# PI.net
KiCad netlist of a schematic drawn in Altium Designer
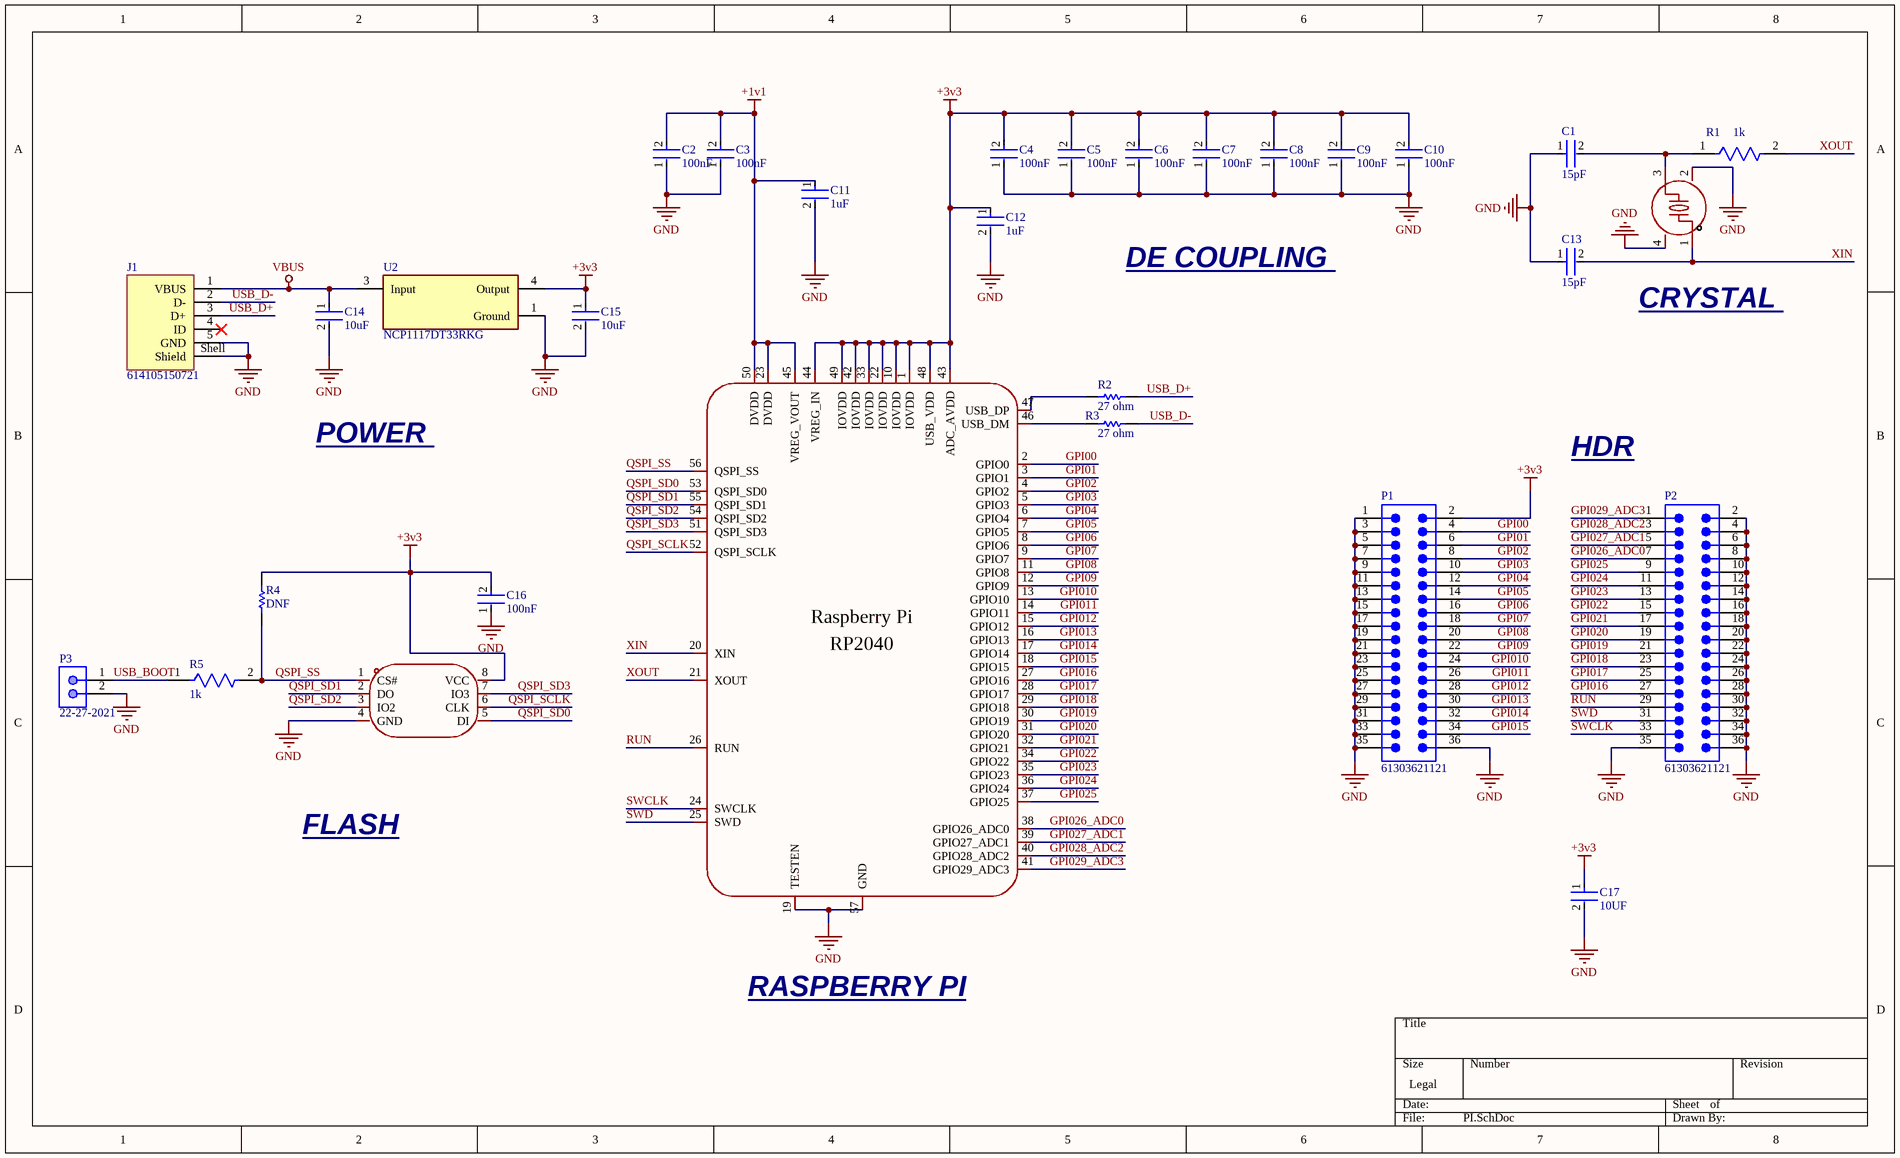
[diagram p0: PI.SchDoc]

(export (version "E")
  (design (tool "Eeschema 10.0.6"))
  (components
    (comp (ref "C1")
      (value "15pF")
      (footprint "FP-C0402-BB-MFG")
      (description "CAP CER 15PF 16V 5% NP0 0402")
      (fields (field (name "MANUFACTURER") "Kemet") (field (name "TOLERANCE") "0.05"))
      (libsource (lib "Altium Content Vault") (part "b4654b650e69147ec39a6b967a45e02"))
    )
    (comp (ref "C2")
      (value "100nF")
      (footprint "FP-GRM15-MFG")
      (description "CAP CER 0.1UF 16V X7R 0402")
      (fields (field (name "MANUFACTURER PART NUMBER") "GRM155R71C104KA88D") (field (name "TOLERANCE") "10%"))
      (libsource (lib "Altium Content Vault") (part "236180d848d6139a670b325ea6854c9"))
    )
    (comp (ref "C3")
      (value "100nF")
      (footprint "FP-GRM15-MFG")
      (description "CAP CER 0.1UF 16V X7R 0402")
      (fields (field (name "MANUFACTURER PART NUMBER") "GRM155R71C104KA88D") (field (name "TOLERANCE") "10%"))
      (libsource (lib "Altium Content Vault") (part "236180d848d6139a670b325ea6854c9"))
    )
    (comp (ref "C4")
      (value "100nF")
      (footprint "FP-GRM15-MFG")
      (description "CAP CER 0.1UF 16V X7R 0402")
      (fields (field (name "MANUFACTURER PART NUMBER") "GRM155R71C104KA88D") (field (name "TOLERANCE") "10%"))
      (libsource (lib "Altium Content Vault") (part "236180d848d6139a670b325ea6854c9"))
    )
    (comp (ref "C5")
      (value "100nF")
      (footprint "FP-GRM15-MFG")
      (description "CAP CER 0.1UF 16V X7R 0402")
      (fields (field (name "MANUFACTURER PART NUMBER") "GRM155R71C104KA88D") (field (name "TOLERANCE") "10%"))
      (libsource (lib "Altium Content Vault") (part "236180d848d6139a670b325ea6854c9"))
    )
    (comp (ref "C6")
      (value "100nF")
      (footprint "FP-GRM15-MFG")
      (description "CAP CER 0.1UF 16V X7R 0402")
      (fields (field (name "MANUFACTURER PART NUMBER") "GRM155R71C104KA88D") (field (name "TOLERANCE") "10%"))
      (libsource (lib "Altium Content Vault") (part "236180d848d6139a670b325ea6854c9"))
    )
    (comp (ref "C7")
      (value "100nF")
      (footprint "FP-GRM15-MFG")
      (description "CAP CER 0.1UF 16V X7R 0402")
      (fields (field (name "MANUFACTURER PART NUMBER") "GRM155R71C104KA88D") (field (name "TOLERANCE") "10%"))
      (libsource (lib "Altium Content Vault") (part "236180d848d6139a670b325ea6854c9"))
    )
    (comp (ref "C8")
      (value "100nF")
      (footprint "FP-GRM15-MFG")
      (description "CAP CER 0.1UF 16V X7R 0402")
      (fields (field (name "MANUFACTURER PART NUMBER") "GRM155R71C104KA88D") (field (name "TOLERANCE") "10%"))
      (libsource (lib "Altium Content Vault") (part "236180d848d6139a670b325ea6854c9"))
    )
    (comp (ref "C9")
      (value "100nF")
      (footprint "FP-GRM15-MFG")
      (description "CAP CER 0.1UF 16V X7R 0402")
      (fields (field (name "MANUFACTURER PART NUMBER") "GRM155R71C104KA88D") (field (name "TOLERANCE") "10%"))
      (libsource (lib "Altium Content Vault") (part "236180d848d6139a670b325ea6854c9"))
    )
    (comp (ref "C10")
      (value "100nF")
      (footprint "FP-GRM15-MFG")
      (description "CAP CER 0.1UF 16V X7R 0402")
      (fields (field (name "MANUFACTURER PART NUMBER") "GRM155R71C104KA88D") (field (name "TOLERANCE") "10%"))
      (libsource (lib "Altium Content Vault") (part "236180d848d6139a670b325ea6854c9"))
    )
    (comp (ref "C11")
      (value "1uF")
      (footprint "FP-C0805C105Z4VACTU-MFG")
      (description "CAP CER 1UF 16V Y5V 0805")
      (fields (field (name "VOLTAGE") "16V") (field (name "TOLERANCE") "80%"))
      (libsource (lib "Altium Content Vault") (part "02cd4be3c70576c341d710602a673aa"))
    )
    (comp (ref "C12")
      (value "1uF")
      (footprint "FP-C0805C105Z4VACTU-MFG")
      (description "CAP CER 1UF 16V Y5V 0805")
      (fields (field (name "VOLTAGE") "16V") (field (name "TOLERANCE") "80%"))
      (libsource (lib "Altium Content Vault") (part "02cd4be3c70576c341d710602a673aa"))
    )
    (comp (ref "C13")
      (value "15pF")
      (footprint "FP-C0402-BB-MFG")
      (description "CAP CER 15PF 16V 5% NP0 0402")
      (fields (field (name "MANUFACTURER") "Kemet") (field (name "TOLERANCE") "0.05"))
      (libsource (lib "Altium Content Vault") (part "b4654b650e69147ec39a6b967a45e02"))
    )
    (comp (ref "C14")
      (value "10uF")
      (footprint "FP-1206-L_3_2_0_2-W_1_6_0-IPC_C")
      (description "General Purpose Ceramic Capacitor, 1206, 10uF, 10%, X7R, 15%, 16V")
      (fields (field (name "VOLTAGE") "16V") (field (name "TOLERANCE") "10%"))
      (libsource (lib "Altium Content Vault") (part "b4654b650e69147ec39a6b967a45e02"))
    )
    (comp (ref "C15")
      (value "10uF")
      (footprint "FP-1206-L_3_2_0_2-W_1_6_0-IPC_C")
      (description "General Purpose Ceramic Capacitor, 1206, 10uF, 10%, X7R, 15%, 16V")
      (fields (field (name "VOLTAGE") "16V") (field (name "TOLERANCE") "10%"))
      (libsource (lib "Altium Content Vault") (part "b4654b650e69147ec39a6b967a45e02"))
    )
    (comp (ref "C16")
      (value "100nF")
      (footprint "FP-GRM15-MFG")
      (description "CAP CER 0.1UF 16V X7R 0402")
      (fields (field (name "MANUFACTURER PART NUMBER") "GRM155R71C104KA88D") (field (name "TOLERANCE") "10%"))
      (libsource (lib "Altium Content Vault") (part "236180d848d6139a670b325ea6854c9"))
    )
    (comp (ref "C17")
      (value "10UF")
      (footprint "FP-0603-L_1_6_0_2-W_0_8_0-MFG")
      (description "Multilayer Ceramic Capacitor 10uF 16V X5R 20% SMD 0603 T/R")
      (fields (field (name "TOLERANCE") "20%"))
      (libsource (lib "Altium Content Vault") (part "b4654b650e69147ec39a6b967a45e02"))
    )
    (comp (ref "J1")
      (value "614105150721")
      (footprint "614105150721")
      (libsource (lib "Altium Content Vault") (part "Micro USB 2.0_Type B_Receptacle_1 Port"))
    )
    (comp (ref "P1")
      (value "61303621121")
      (footprint "61303621121")
      (libsource (lib "Altium Content Vault") (part "Header_Male_2R_36P"))
    )
    (comp (ref "P2")
      (value "61303621121")
      (footprint "61303621121")
      (libsource (lib "Altium Content Vault") (part "Header_Male_2R_36P"))
    )
    (comp (ref "P3")
      (value "22-27-2021")
      (footprint "MOLX-22-27-2021_V")
      (fields (field (name "MANUFACTURER") "Molex") (field (name "PARTNUMBER") "0022272021"))
      (libsource (lib "Altium Content Vault") (part "CN-1P-M-R2"))
    )
    (comp (ref "R1")
      (value "1k")
      (footprint "FP-AC0603-IPC_B")
      (description "RES 1kΩ 1.00% 0.1W 0603")
      (fields (field (name "TOLERANCE") "1%"))
      (libsource (lib "Altium Content Vault") (part "1029c3af85768c4190bb7ad29bc67b5"))
    )
    (comp (ref "R2")
      (value "27 ohm")
      (footprint "RESC1005X40X25LL05T10")
      (fields (field (name "PART NUMBER") "RC0402FR-0727RL") (field (name "MANUFACTURER") "Yageo / Phycomp"))
      (libsource (lib "Altium Content Vault") (part "RES"))
    )
    (comp (ref "R3")
      (value "27 ohm")
      (footprint "RESC1005X40X25LL05T10")
      (fields (field (name "PART NUMBER") "RC0402FR-0727RL") (field (name "MANUFACTURER") "Yageo / Phycomp"))
      (libsource (lib "Altium Content Vault") (part "RES"))
    )
    (comp (ref "R4")
      (value "DNF")
      (footprint "RESC2013X50X30LL20T20")
      (fields (field (name "MANUFACTURER") "Vishay Dale") (field (name "PART NUMBER") "CRCW08050000Z0EA"))
      (libsource (lib "Altium Content Vault") (part "RES"))
    )
    (comp (ref "R5")
      (value "1k")
      (footprint "FP-AC0603-IPC_B")
      (description "RES 1kΩ 1.00% 0.1W 0603")
      (fields (field (name "TOLERANCE") "1%"))
      (libsource (lib "Altium Content Vault") (part "1029c3af85768c4190bb7ad29bc67b5"))
    )
    (comp (ref "U1")
      (value "ABM8-272-T3")
      (footprint "CRYSTAL-SMD_4P-L3.2-W2.5-BL")
      (fields (field (name "MANUFACTURER") "ABRACON"))
      (libsource (lib "RP") (part "ABM8-272-T3_C20625731"))
    )
    (comp (ref "U2")
      (value "NCP1117DT33RKG")
      (footprint "FP-369C-MFG")
      (description "IC REG LINEAR 3.3V 1A DPAK-3")
      (libsource (lib "Altium Content Vault") (part "42bbf5c8e4ae9854764b07c869d8ce2"))
    )
    (comp (ref "U3")
      (value "RP2040")
      (footprint "LQFN-56_L7.0-W7.0-P0.4-EP")
      (fields (field (name "MANUFACTURER") "Raspberry Pi(树莓派)"))
      (libsource (lib "RP") (part "RP2040_C2040"))
    )
    (comp (ref "U4")
      (value "W25Q128JVSIQ")
      (footprint "SOIC-8_L5.3-W5.3-P1.27-LS8.0-BL")
      (fields (field (name "MANUFACTURER") "WINBOND(华邦)"))
      (libsource (lib "RP") (part "W25Q128JVSIQ"))
    )
  )
  (nets
    (net (code "1") (name "+1v1") (class "Default")
      (node (ref "C11") (pin "1") (pinfunction "1_1") (pintype "passive"))
      (node (ref "C2") (pin "2") (pinfunction "2_2") (pintype "passive"))
      (node (ref "C3") (pin "2") (pinfunction "2_2") (pintype "passive"))
      (node (ref "U3") (pin "23") (pinfunction "DVDD_23") (pintype "passive"))
      (node (ref "U3") (pin "45") (pinfunction "VREG_VOUT_45") (pintype "passive"))
      (node (ref "U3") (pin "50") (pinfunction "DVDD_50") (pintype "passive"))
    )
    (net (code "2") (name "+3v3") (class "Default")
      (node (ref "C10") (pin "2") (pinfunction "2_2") (pintype "passive"))
      (node (ref "C12") (pin "1") (pinfunction "1_1") (pintype "passive"))
      (node (ref "C15") (pin "1") (pinfunction "1_1") (pintype "passive"))
      (node (ref "C16") (pin "2") (pinfunction "2_2") (pintype "passive"))
      (node (ref "C17") (pin "1") (pinfunction "1_1") (pintype "passive"))
      (node (ref "C4") (pin "2") (pinfunction "2_2") (pintype "passive"))
      (node (ref "C5") (pin "2") (pinfunction "2_2") (pintype "passive"))
      (node (ref "C6") (pin "2") (pinfunction "2_2") (pintype "passive"))
      (node (ref "C7") (pin "2") (pinfunction "2_2") (pintype "passive"))
      (node (ref "C8") (pin "2") (pinfunction "2_2") (pintype "passive"))
      (node (ref "C9") (pin "2") (pinfunction "2_2") (pintype "passive"))
      (node (ref "P1") (pin "2") (pinfunction "2_2") (pintype "passive"))
      (node (ref "R4") (pin "2") (pinfunction "2_2") (pintype "passive"))
      (node (ref "U2") (pin "4") (pinfunction "Output_4") (pintype "power_in"))
      (node (ref "U3") (pin "1") (pinfunction "IOVDD_1") (pintype "passive"))
      (node (ref "U3") (pin "10") (pinfunction "IOVDD_10") (pintype "passive"))
      (node (ref "U3") (pin "22") (pinfunction "IOVDD_22") (pintype "passive"))
      (node (ref "U3") (pin "33") (pinfunction "IOVDD_33") (pintype "passive"))
      (node (ref "U3") (pin "42") (pinfunction "IOVDD_42") (pintype "passive"))
      (node (ref "U3") (pin "43") (pinfunction "ADC_AVDD_43") (pintype "passive"))
      (node (ref "U3") (pin "44") (pinfunction "VREG_IN_44") (pintype "passive"))
      (node (ref "U3") (pin "48") (pinfunction "USB_VDD_48") (pintype "passive"))
      (node (ref "U3") (pin "49") (pinfunction "IOVDD_49") (pintype "passive"))
      (node (ref "U4") (pin "8") (pinfunction "VCC_8") (pintype "passive"))
    )
    (net (code "3") (name "/GPI00") (class "Default")
      (node (ref "P1") (pin "4") (pinfunction "4_4") (pintype "passive"))
      (node (ref "U3") (pin "2") (pinfunction "GPIO0_2") (pintype "passive"))
    )
    (net (code "4") (name "/GPI01") (class "Default")
      (node (ref "P1") (pin "6") (pinfunction "6_6") (pintype "passive"))
      (node (ref "U3") (pin "3") (pinfunction "GPIO1_3") (pintype "passive"))
    )
    (net (code "5") (name "/GPI02") (class "Default")
      (node (ref "P1") (pin "8") (pinfunction "8_8") (pintype "passive"))
      (node (ref "U3") (pin "4") (pinfunction "GPIO2_4") (pintype "passive"))
    )
    (net (code "6") (name "/GPI03") (class "Default")
      (node (ref "P1") (pin "10") (pinfunction "10_10") (pintype "passive"))
      (node (ref "U3") (pin "5") (pinfunction "GPIO3_5") (pintype "passive"))
    )
    (net (code "7") (name "/GPI04") (class "Default")
      (node (ref "P1") (pin "12") (pinfunction "12_12") (pintype "passive"))
      (node (ref "U3") (pin "6") (pinfunction "GPIO4_6") (pintype "passive"))
    )
    (net (code "8") (name "/GPI05") (class "Default")
      (node (ref "P1") (pin "14") (pinfunction "14_14") (pintype "passive"))
      (node (ref "U3") (pin "7") (pinfunction "GPIO5_7") (pintype "passive"))
    )
    (net (code "9") (name "/GPI06") (class "Default")
      (node (ref "P1") (pin "16") (pinfunction "16_16") (pintype "passive"))
      (node (ref "U3") (pin "8") (pinfunction "GPIO6_8") (pintype "passive"))
    )
    (net (code "10") (name "/GPI07") (class "Default")
      (node (ref "P1") (pin "18") (pinfunction "18_18") (pintype "passive"))
      (node (ref "U3") (pin "9") (pinfunction "GPIO7_9") (pintype "passive"))
    )
    (net (code "11") (name "/GPI08") (class "Default")
      (node (ref "P1") (pin "20") (pinfunction "20_20") (pintype "passive"))
      (node (ref "U3") (pin "11") (pinfunction "GPIO8_11") (pintype "passive"))
    )
    (net (code "12") (name "/GPI09") (class "Default")
      (node (ref "P1") (pin "22") (pinfunction "22_22") (pintype "passive"))
      (node (ref "U3") (pin "12") (pinfunction "GPIO9_12") (pintype "passive"))
    )
    (net (code "13") (name "/GPI010") (class "Default")
      (node (ref "P1") (pin "24") (pinfunction "24_24") (pintype "passive"))
      (node (ref "U3") (pin "13") (pinfunction "GPIO10_13") (pintype "passive"))
    )
    (net (code "14") (name "/GPI011") (class "Default")
      (node (ref "P1") (pin "26") (pinfunction "26_26") (pintype "passive"))
      (node (ref "U3") (pin "14") (pinfunction "GPIO11_14") (pintype "passive"))
    )
    (net (code "15") (name "/GPI012") (class "Default")
      (node (ref "P1") (pin "28") (pinfunction "28_28") (pintype "passive"))
      (node (ref "U3") (pin "15") (pinfunction "GPIO12_15") (pintype "passive"))
    )
    (net (code "16") (name "/GPI013") (class "Default")
      (node (ref "P1") (pin "30") (pinfunction "30_30") (pintype "passive"))
      (node (ref "U3") (pin "16") (pinfunction "GPIO13_16") (pintype "passive"))
    )
    (net (code "17") (name "/GPI014") (class "Default")
      (node (ref "P1") (pin "32") (pinfunction "32_32") (pintype "passive"))
      (node (ref "U3") (pin "17") (pinfunction "GPIO14_17") (pintype "passive"))
    )
    (net (code "18") (name "/GPI015") (class "Default")
      (node (ref "P1") (pin "34") (pinfunction "34_34") (pintype "passive"))
      (node (ref "U3") (pin "18") (pinfunction "GPIO15_18") (pintype "passive"))
    )
    (net (code "19") (name "/GPI016") (class "Default")
      (node (ref "P2") (pin "27") (pinfunction "27_27") (pintype "passive"))
      (node (ref "U3") (pin "27") (pinfunction "GPIO16_27") (pintype "passive"))
    )
    (net (code "20") (name "/GPI017") (class "Default")
      (node (ref "P2") (pin "25") (pinfunction "25_25") (pintype "passive"))
      (node (ref "U3") (pin "28") (pinfunction "GPIO17_28") (pintype "passive"))
    )
    (net (code "21") (name "/GPI018") (class "Default")
      (node (ref "P2") (pin "23") (pinfunction "23_23") (pintype "passive"))
      (node (ref "U3") (pin "29") (pinfunction "GPIO18_29") (pintype "passive"))
    )
    (net (code "22") (name "/GPI019") (class "Default")
      (node (ref "P2") (pin "21") (pinfunction "21_21") (pintype "passive"))
      (node (ref "U3") (pin "30") (pinfunction "GPIO19_30") (pintype "passive"))
    )
    (net (code "23") (name "/GPI020") (class "Default")
      (node (ref "P2") (pin "19") (pinfunction "19_19") (pintype "passive"))
      (node (ref "U3") (pin "31") (pinfunction "GPIO20_31") (pintype "passive"))
    )
    (net (code "24") (name "/GPI021") (class "Default")
      (node (ref "P2") (pin "17") (pinfunction "17_17") (pintype "passive"))
      (node (ref "U3") (pin "32") (pinfunction "GPIO21_32") (pintype "passive"))
    )
    (net (code "25") (name "/GPI022") (class "Default")
      (node (ref "P2") (pin "15") (pinfunction "15_15") (pintype "passive"))
      (node (ref "U3") (pin "34") (pinfunction "GPIO22_34") (pintype "passive"))
    )
    (net (code "26") (name "/GPI023") (class "Default")
      (node (ref "P2") (pin "13") (pinfunction "13_13") (pintype "passive"))
      (node (ref "U3") (pin "35") (pinfunction "GPIO23_35") (pintype "passive"))
    )
    (net (code "27") (name "/GPI024") (class "Default")
      (node (ref "P2") (pin "11") (pinfunction "11_11") (pintype "passive"))
      (node (ref "U3") (pin "36") (pinfunction "GPIO24_36") (pintype "passive"))
    )
    (net (code "28") (name "/GPI025") (class "Default")
      (node (ref "P2") (pin "9") (pinfunction "9_9") (pintype "passive"))
      (node (ref "U3") (pin "37") (pinfunction "GPIO25_37") (pintype "passive"))
    )
    (net (code "29") (name "/GPI026_ADC0") (class "Default")
      (node (ref "P2") (pin "7") (pinfunction "7_7") (pintype "passive"))
      (node (ref "U3") (pin "38") (pinfunction "GPIO26_ADC0_38") (pintype "passive"))
    )
    (net (code "30") (name "/GPI027_ADC1") (class "Default")
      (node (ref "P2") (pin "5") (pinfunction "5_5") (pintype "passive"))
      (node (ref "U3") (pin "39") (pinfunction "GPIO27_ADC1_39") (pintype "passive"))
    )
    (net (code "31") (name "/GPI028_ADC2") (class "Default")
      (node (ref "P2") (pin "3") (pinfunction "3_3") (pintype "passive"))
      (node (ref "U3") (pin "40") (pinfunction "GPIO28_ADC2_40") (pintype "passive"))
    )
    (net (code "32") (name "/GPI029_ADC3") (class "Default")
      (node (ref "P2") (pin "1") (pinfunction "1_1") (pintype "passive"))
      (node (ref "U3") (pin "41") (pinfunction "GPIO29_ADC3_41") (pintype "passive"))
    )
    (net (code "33") (name "/QSPI_SCLK") (class "Default")
      (node (ref "U3") (pin "52") (pinfunction "QSPI_SCLK_52") (pintype "passive"))
      (node (ref "U4") (pin "6") (pinfunction "CLK_6") (pintype "passive"))
    )
    (net (code "34") (name "/QSPI_SD0") (class "Default")
      (node (ref "U3") (pin "53") (pinfunction "QSPI_SD0_53") (pintype "passive"))
      (node (ref "U4") (pin "5") (pinfunction "DI_5") (pintype "passive"))
    )
    (net (code "35") (name "/QSPI_SD1") (class "Default")
      (node (ref "U3") (pin "55") (pinfunction "QSPI_SD1_55") (pintype "passive"))
      (node (ref "U4") (pin "2") (pinfunction "DO_2") (pintype "passive"))
    )
    (net (code "36") (name "/QSPI_SD2") (class "Default")
      (node (ref "U3") (pin "54") (pinfunction "QSPI_SD2_54") (pintype "passive"))
      (node (ref "U4") (pin "3") (pinfunction "IO2_3") (pintype "passive"))
    )
    (net (code "37") (name "/QSPI_SD3") (class "Default")
      (node (ref "U3") (pin "51") (pinfunction "QSPI_SD3_51") (pintype "passive"))
      (node (ref "U4") (pin "7") (pinfunction "IO3_7") (pintype "passive"))
    )
    (net (code "38") (name "/QSPI_SS") (class "Default")
      (node (ref "R4") (pin "1") (pinfunction "1_1") (pintype "passive"))
      (node (ref "R5") (pin "2") (pinfunction "2_2") (pintype "passive"))
      (node (ref "U3") (pin "56") (pinfunction "QSPI_SS_56") (pintype "passive"))
      (node (ref "U4") (pin "1") (pinfunction "CS#_1") (pintype "passive"))
    )
    (net (code "39") (name "/RUN") (class "Default")
      (node (ref "P2") (pin "29") (pinfunction "29_29") (pintype "passive"))
      (node (ref "U3") (pin "26") (pinfunction "RUN_26") (pintype "passive"))
    )
    (net (code "40") (name "/SWCLK") (class "Default")
      (node (ref "P2") (pin "33") (pinfunction "33_33") (pintype "passive"))
      (node (ref "U3") (pin "24") (pinfunction "SWCLK_24") (pintype "passive"))
    )
    (net (code "41") (name "/SWD") (class "Default")
      (node (ref "P2") (pin "31") (pinfunction "31_31") (pintype "passive"))
      (node (ref "U3") (pin "25") (pinfunction "SWD_25") (pintype "passive"))
    )
    (net (code "42") (name "/USB_BOOT") (class "Default")
      (node (ref "P3") (pin "1") (pinfunction "1_1") (pintype "passive"))
      (node (ref "R5") (pin "1") (pinfunction "1_1") (pintype "passive"))
    )
    (net (code "43") (name "/USB_D+") (class "Default")
      (node (ref "J1") (pin "3") (pinfunction "D+_3") (pintype "passive"))
      (node (ref "R2") (pin "2") (pinfunction "2_2") (pintype "passive"))
    )
    (net (code "44") (name "/USB_D-") (class "Default")
      (node (ref "J1") (pin "2") (pinfunction "D-_2") (pintype "passive"))
      (node (ref "R3") (pin "2") (pinfunction "2_2") (pintype "passive"))
    )
    (net (code "45") (name "/XIN") (class "Default")
      (node (ref "C13") (pin "2") (pinfunction "2_2") (pintype "passive"))
      (node (ref "U1") (pin "1") (pinfunction "1_1") (pintype "passive"))
      (node (ref "U3") (pin "20") (pinfunction "XIN_20") (pintype "passive"))
    )
    (net (code "46") (name "/XOUT") (class "Default")
      (node (ref "R1") (pin "2") (pinfunction "2_2") (pintype "passive"))
      (node (ref "U3") (pin "21") (pinfunction "XOUT_21") (pintype "passive"))
    )
    (net (code "47") (name "GND") (class "Default")
      (node (ref "C1") (pin "1") (pinfunction "1_1") (pintype "passive"))
      (node (ref "C10") (pin "1") (pinfunction "1_1") (pintype "passive"))
      (node (ref "C11") (pin "2") (pinfunction "2_2") (pintype "passive"))
      (node (ref "C12") (pin "2") (pinfunction "2_2") (pintype "passive"))
      (node (ref "C13") (pin "1") (pinfunction "1_1") (pintype "passive"))
      (node (ref "C14") (pin "2") (pinfunction "2_2") (pintype "passive"))
      (node (ref "C15") (pin "2") (pinfunction "2_2") (pintype "passive"))
      (node (ref "C16") (pin "1") (pinfunction "1_1") (pintype "passive"))
      (node (ref "C17") (pin "2") (pinfunction "2_2") (pintype "passive"))
      (node (ref "C2") (pin "1") (pinfunction "1_1") (pintype "passive"))
      (node (ref "C3") (pin "1") (pinfunction "1_1") (pintype "passive"))
      (node (ref "C4") (pin "1") (pinfunction "1_1") (pintype "passive"))
      (node (ref "C5") (pin "1") (pinfunction "1_1") (pintype "passive"))
      (node (ref "C6") (pin "1") (pinfunction "1_1") (pintype "passive"))
      (node (ref "C7") (pin "1") (pinfunction "1_1") (pintype "passive"))
      (node (ref "C8") (pin "1") (pinfunction "1_1") (pintype "passive"))
      (node (ref "C9") (pin "1") (pinfunction "1_1") (pintype "passive"))
      (node (ref "J1") (pin "5") (pinfunction "GND_5") (pintype "passive"))
      (node (ref "J1") (pin "Shell") (pinfunction "Shield_Shell") (pintype "passive"))
      (node (ref "P1") (pin "1") (pinfunction "1_1") (pintype "passive"))
      (node (ref "P1") (pin "11") (pinfunction "11_11") (pintype "passive"))
      (node (ref "P1") (pin "13") (pinfunction "13_13") (pintype "passive"))
      (node (ref "P1") (pin "15") (pinfunction "15_15") (pintype "passive"))
      (node (ref "P1") (pin "17") (pinfunction "17_17") (pintype "passive"))
      (node (ref "P1") (pin "19") (pinfunction "19_19") (pintype "passive"))
      (node (ref "P1") (pin "21") (pinfunction "21_21") (pintype "passive"))
      (node (ref "P1") (pin "23") (pinfunction "23_23") (pintype "passive"))
      (node (ref "P1") (pin "25") (pinfunction "25_25") (pintype "passive"))
      (node (ref "P1") (pin "27") (pinfunction "27_27") (pintype "passive"))
      (node (ref "P1") (pin "29") (pinfunction "29_29") (pintype "passive"))
      (node (ref "P1") (pin "3") (pinfunction "3_3") (pintype "passive"))
      (node (ref "P1") (pin "31") (pinfunction "31_31") (pintype "passive"))
      (node (ref "P1") (pin "33") (pinfunction "33_33") (pintype "passive"))
      (node (ref "P1") (pin "35") (pinfunction "35_35") (pintype "passive"))
      (node (ref "P1") (pin "36") (pinfunction "36_36") (pintype "passive"))
      (node (ref "P1") (pin "5") (pinfunction "5_5") (pintype "passive"))
      (node (ref "P1") (pin "7") (pinfunction "7_7") (pintype "passive"))
      (node (ref "P1") (pin "9") (pinfunction "9_9") (pintype "passive"))
      (node (ref "P2") (pin "10") (pinfunction "10_10") (pintype "passive"))
      (node (ref "P2") (pin "12") (pinfunction "12_12") (pintype "passive"))
      (node (ref "P2") (pin "14") (pinfunction "14_14") (pintype "passive"))
      (node (ref "P2") (pin "16") (pinfunction "16_16") (pintype "passive"))
      (node (ref "P2") (pin "18") (pinfunction "18_18") (pintype "passive"))
      (node (ref "P2") (pin "2") (pinfunction "2_2") (pintype "passive"))
      (node (ref "P2") (pin "20") (pinfunction "20_20") (pintype "passive"))
      (node (ref "P2") (pin "22") (pinfunction "22_22") (pintype "passive"))
      (node (ref "P2") (pin "24") (pinfunction "24_24") (pintype "passive"))
      (node (ref "P2") (pin "26") (pinfunction "26_26") (pintype "passive"))
      (node (ref "P2") (pin "28") (pinfunction "28_28") (pintype "passive"))
      (node (ref "P2") (pin "30") (pinfunction "30_30") (pintype "passive"))
      (node (ref "P2") (pin "32") (pinfunction "32_32") (pintype "passive"))
      (node (ref "P2") (pin "34") (pinfunction "34_34") (pintype "passive"))
      (node (ref "P2") (pin "35") (pinfunction "35_35") (pintype "passive"))
      (node (ref "P2") (pin "36") (pinfunction "36_36") (pintype "passive"))
      (node (ref "P2") (pin "4") (pinfunction "4_4") (pintype "passive"))
      (node (ref "P2") (pin "6") (pinfunction "6_6") (pintype "passive"))
      (node (ref "P2") (pin "8") (pinfunction "8_8") (pintype "passive"))
      (node (ref "P3") (pin "2") (pinfunction "2_2") (pintype "passive"))
      (node (ref "U1") (pin "2") (pinfunction "GND_2") (pintype "passive"))
      (node (ref "U1") (pin "4") (pinfunction "GND_4") (pintype "passive"))
      (node (ref "U2") (pin "1") (pinfunction "Ground_1") (pintype "power_in"))
      (node (ref "U3") (pin "19") (pinfunction "TESTEN_19") (pintype "passive"))
      (node (ref "U3") (pin "57") (pinfunction "GND_57") (pintype "passive"))
      (node (ref "U4") (pin "4") (pinfunction "GND_4") (pintype "passive"))
    )
    (net (code "48") (name "Net-(C1-Pad2)") (class "Default")
      (node (ref "C1") (pin "2") (pinfunction "2_2") (pintype "passive"))
      (node (ref "R1") (pin "1") (pinfunction "1_1") (pintype "passive"))
      (node (ref "U1") (pin "3") (pinfunction "3_3") (pintype "passive"))
    )
    (net (code "49") (name "Net-(U3-USB_DM)") (class "Default")
      (node (ref "R3") (pin "1") (pinfunction "1_1") (pintype "passive"))
      (node (ref "U3") (pin "46") (pinfunction "USB_DM_46") (pintype "passive"))
    )
    (net (code "50") (name "Net-(U3-USB_DP)") (class "Default")
      (node (ref "R2") (pin "1") (pinfunction "1_1") (pintype "passive"))
      (node (ref "U3") (pin "47") (pinfunction "USB_DP_47") (pintype "passive"))
    )
    (net (code "51") (name "VBUS") (class "Default")
      (node (ref "C14") (pin "1") (pinfunction "1_1") (pintype "passive"))
      (node (ref "J1") (pin "1") (pinfunction "VBUS_1") (pintype "passive"))
      (node (ref "U2") (pin "3") (pinfunction "Input_3") (pintype "power_in"))
    )
    (net (code "52") (name "unconnected-(J1-ID-Pad4)") (class "Default")
      (node (ref "J1") (pin "4") (pinfunction "ID_4") (pintype "passive+no_connect"))
    )
  )
)
